# 1-Schematic_CarFan_controller_v2_3.net
KiCad netlist of a schematic drawn in EasyEDA
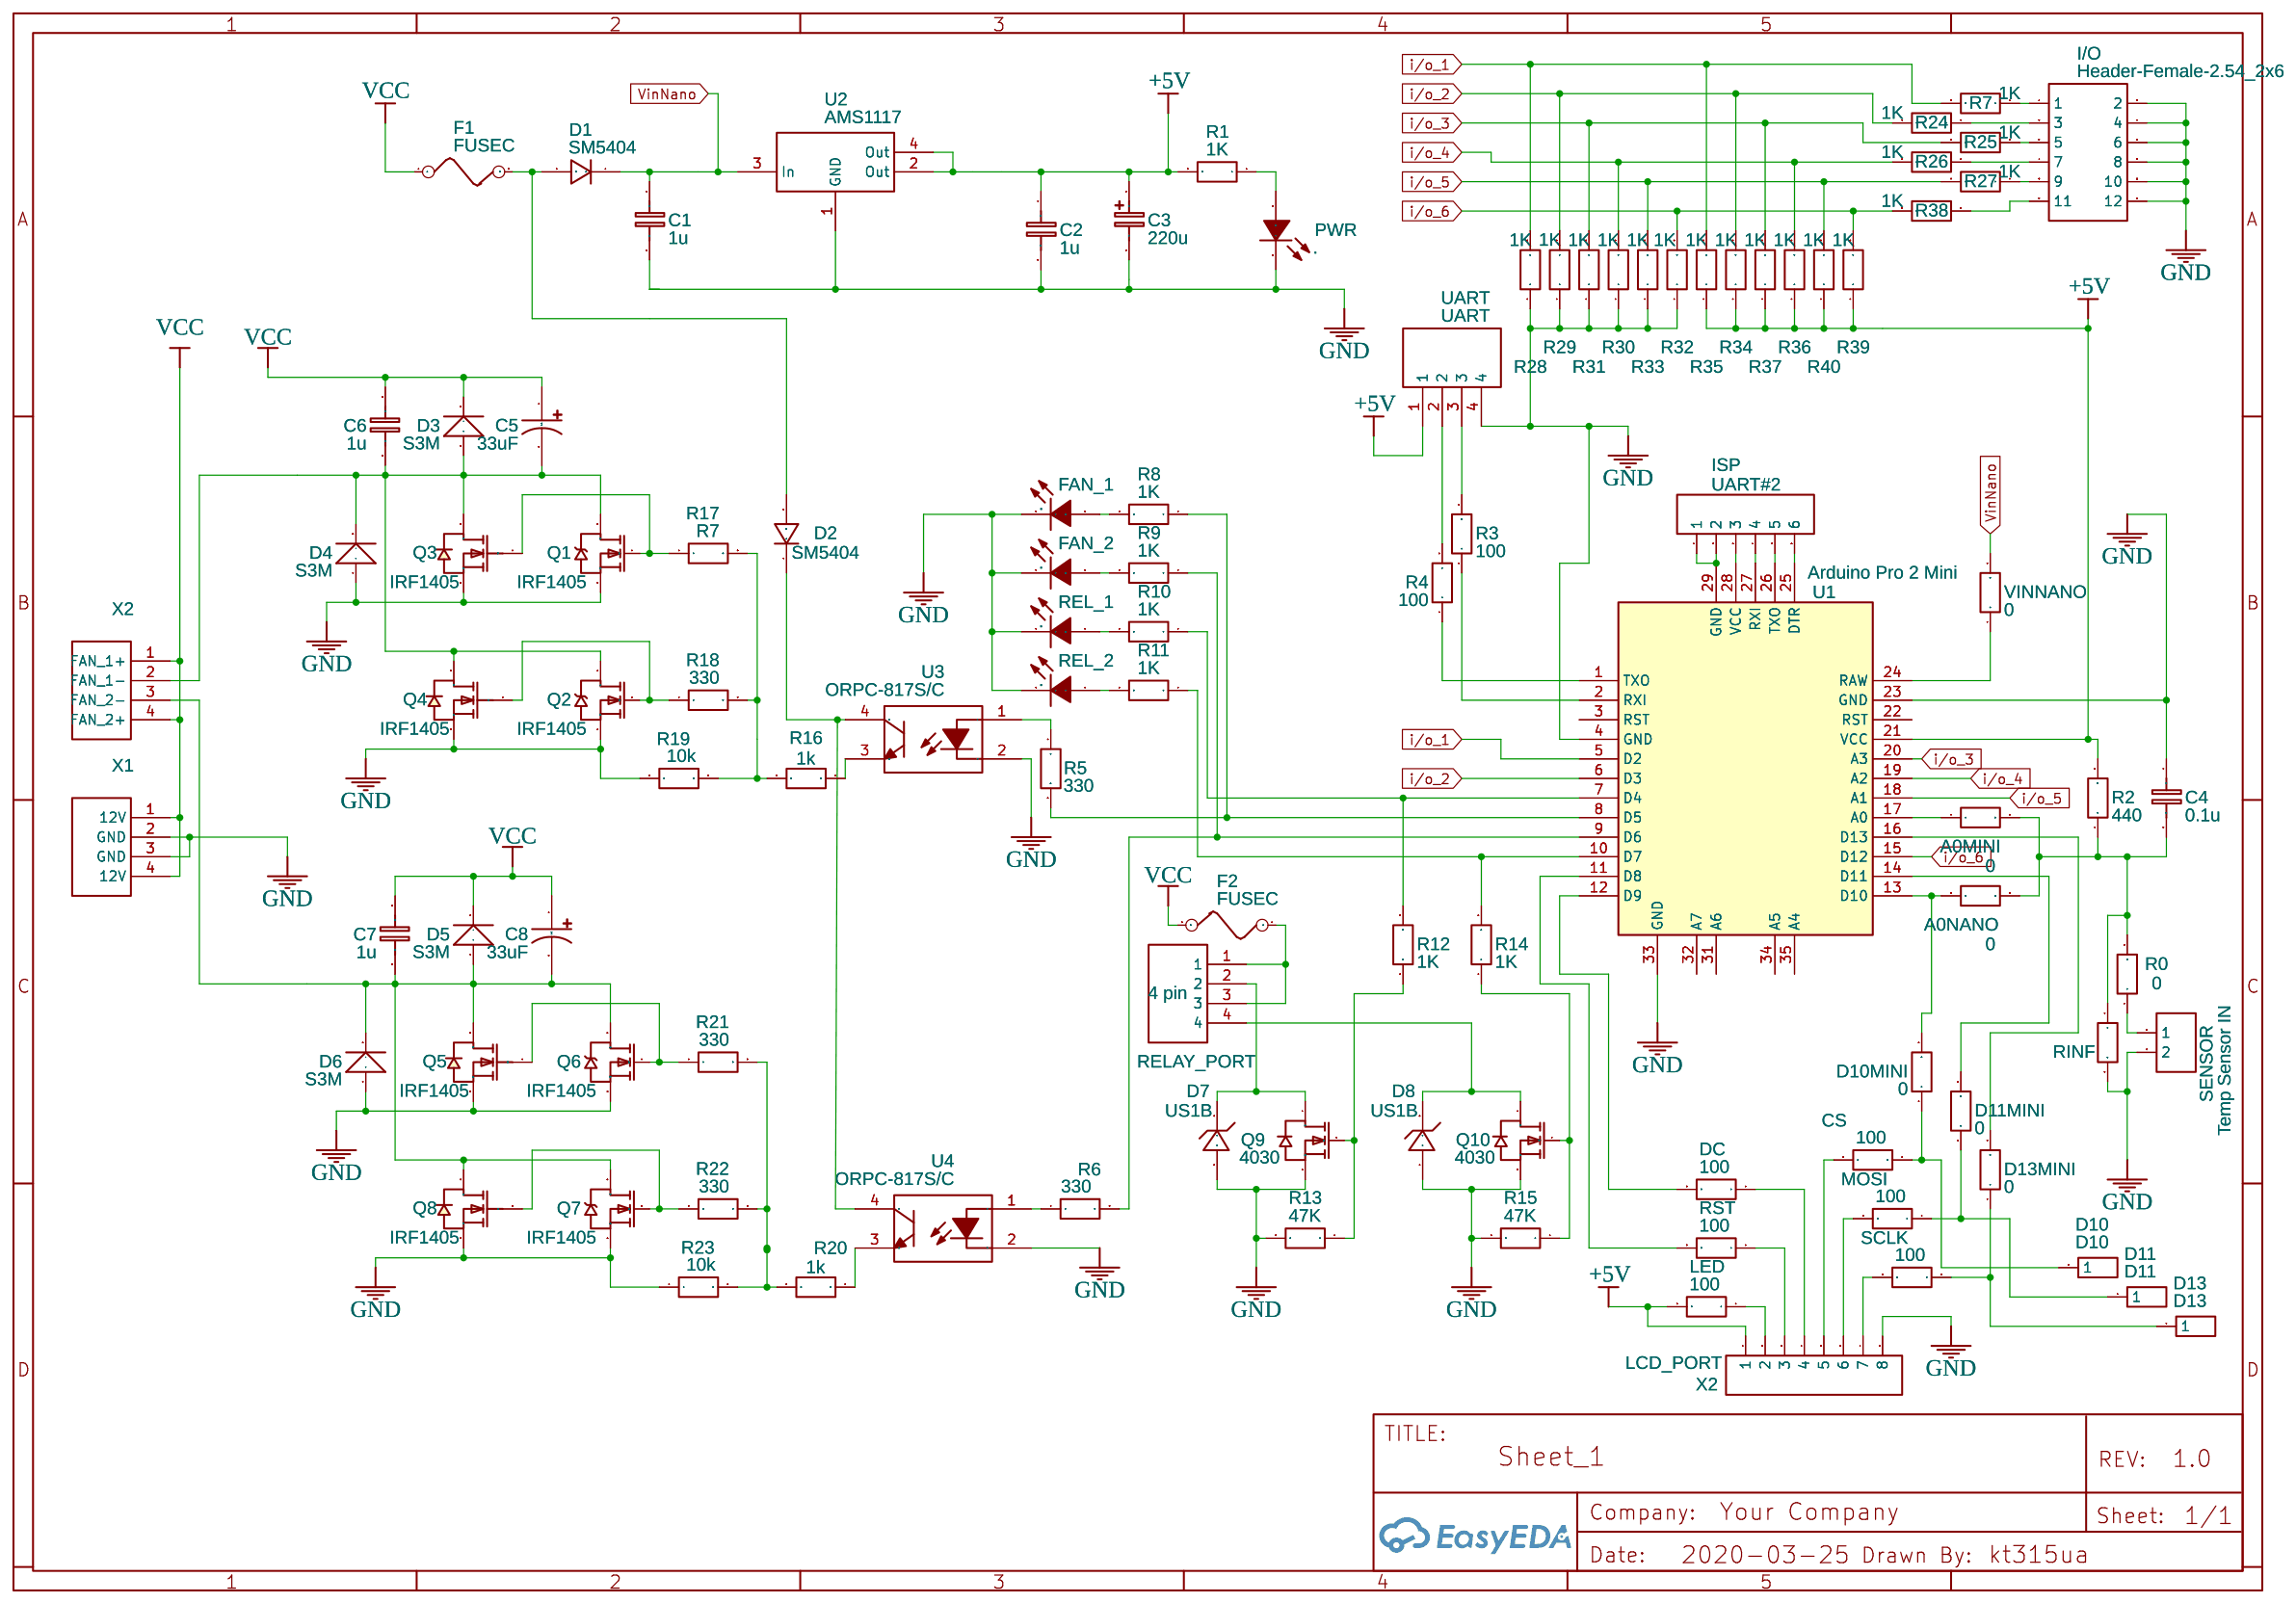
[diagram p0: schematic sheet]

(export (version "E")
  (design (tool "Eeschema 10.0.6"))
  (components
    (comp (ref "A0MINI") (value "0") (libsource (lib "") (part "Res_1206(1/4W)_EU_15")))
    (comp (ref "A0NANO") (value "0") (libsource (lib "") (part "Res_1206(1/4W)_EU_14")))
    (comp (ref "C1") (value "1u") (libsource (lib "") (part "Cap_1206_EU_3")))
    (comp (ref "C2") (value "1u") (libsource (lib "") (part "Cap_1206_EU_1")))
    (comp (ref "C3") (value "220u") (libsource (lib "") (part "Cap_Electrolytic(SMD)_D6.3XH5.5_EU")))
    (comp (ref "C4") (value "0.1u") (libsource (lib "") (part "Cap_1206_EU")))
    (comp (ref "C5")
      (value "33uF")
      (fields
        (field (name "BOM_Manufacturer Part") "EEEFK2A330P")
        (field (name "BOM_Supplier Part") "C178571")
      )
      (libsource (lib "") (part "EEEFK2A330P"))
    )
    (comp (ref "C6") (value "1u") (libsource (lib "") (part "Cap_1206_EU_2")))
    (comp (ref "C7") (value "1u") (libsource (lib "") (part "Cap_1206_EU_4")))
    (comp (ref "C8")
      (value "33uF")
      (fields
        (field (name "BOM_Manufacturer Part") "EEEFK2A330P")
        (field (name "BOM_Supplier Part") "C178571")
      )
      (libsource (lib "") (part "EEEFK2A330P"))
    )
    (comp (ref "CS") (value "100") (libsource (lib "") (part "Res_1206(1/4W)_EU_5")))
    (comp (ref "D1")
      (value "SM5404")
      (fields (field (name "BOM_Supplier Part") "C212808"))
      (libsource (lib "") (part "SM5404"))
    )
    (comp (ref "D2")
      (value "SM5404")
      (fields (field (name "BOM_Supplier Part") "C212808"))
      (libsource (lib "") (part "SM5404_1"))
    )
    (comp (ref "D3") (value "S3M") (libsource (lib "") (part "DDO-214AB")))
    (comp (ref "D4") (value "S3M") (libsource (lib "") (part "DDO-214AB")))
    (comp (ref "D5") (value "S3M") (libsource (lib "") (part "DDO-214AB")))
    (comp (ref "D6") (value "S3M") (libsource (lib "") (part "DDO-214AB")))
    (comp (ref "D7")
      (value "US1B")
      (fields
        (field (name "BOM_Manufacturer Part") "SMAZ12-13-F")
        (field (name "BOM_Supplier Part") "C110523")
      )
      (libsource (lib "") (part "SMAZ12-13-F(SMA(DO-214AC))"))
    )
    (comp (ref "D8")
      (value "US1B")
      (fields
        (field (name "BOM_Manufacturer Part") "SMAZ12-13-F")
        (field (name "BOM_Supplier Part") "C110523")
      )
      (libsource (lib "") (part "SMAZ12-13-F(SMA(DO-214AC))"))
    )
    (comp (ref "D10")
      (value "D10")
      (fields
        (field (name "BOM_Manufacturer Part") "Header-Male-2.54_1x1")
        (field (name "BOM_Supplier Part") "C81276")
      )
      (libsource (lib "") (part "Header-Male-2.54_1x1"))
    )
    (comp (ref "D10MINI") (value "0") (libsource (lib "") (part "Res_1206(1/4W)_EU_16")))
    (comp (ref "D11")
      (value "D11")
      (fields
        (field (name "BOM_Manufacturer Part") "Header-Male-2.54_1x1")
        (field (name "BOM_Supplier Part") "C81276")
      )
      (libsource (lib "") (part "Header-Male-2.54_1x1"))
    )
    (comp (ref "D11MINI") (value "0") (libsource (lib "") (part "Res_1206(1/4W)_EU_6")))
    (comp (ref "D13")
      (value "D13")
      (fields
        (field (name "BOM_Manufacturer Part") "Header-Male-2.54_1x1")
        (field (name "BOM_Supplier Part") "C81276")
      )
      (libsource (lib "") (part "Header-Male-2.54_1x1"))
    )
    (comp (ref "D13MINI") (value "0") (libsource (lib "") (part "Res_1206(1/4W)_EU_7")))
    (comp (ref "DC") (value "100") (libsource (lib "") (part "Res_1206(1/4W)_EU_12")))
    (comp (ref "F1") (value "FUSEC") (libsource (lib "") (part "FUSEC_1")))
    (comp (ref "F2") (value "FUSEC") (libsource (lib "") (part "FUSEC")))
    (comp (ref "FAN_1")
      (value ".")
      (fields
        (field (name "BOM_Manufacturer Part") "KT-1206Red LED")
        (field (name "BOM_Supplier Part") "C49018")
      )
      (libsource (lib "") (part "KT-1206Red LED_2"))
    )
    (comp (ref "FAN_2")
      (value ".")
      (fields
        (field (name "BOM_Manufacturer Part") "KT-1206Red LED")
        (field (name "BOM_Supplier Part") "C49018")
      )
      (libsource (lib "") (part "KT-1206Red LED_2"))
    )
    (comp (ref "I/O")
      (value "Header-Female-2.54_2x6")
      (fields (field (name "BOM_Supplier Part") "C36191"))
      (libsource (lib "") (part "Header-Female-2.54_2x6"))
    )
    (comp (ref "ISP")
      (value "UART#2")
      (fields
        (field (name "BOM_Manufacturer Part") "Female header 1*6p")
        (field (name "BOM_Supplier Part") "C40877")
      )
      (libsource (lib "") (part "Header-Female-2.54_1x6"))
    )
    (comp (ref "LCD_PORT")
      (value "X2")
      (fields
        (field (name "BOM_Manufacturer Part") "Female headerHDR1X8-2.54")
        (field (name "BOM_Supplier Part") "C27438")
      )
      (libsource (lib "") (part "Header-Female-2.54_1x8"))
    )
    (comp (ref "LED") (value "100") (libsource (lib "") (part "Res_1206(1/4W)_EU_9")))
    (comp (ref "MOSI") (value "100") (libsource (lib "") (part "Res_1206(1/4W)_EU_8")))
    (comp (ref "PWR")
      (value ".")
      (fields
        (field (name "BOM_Manufacturer Part") "KT-1206Red LED")
        (field (name "BOM_Supplier Part") "C49018")
      )
      (libsource (lib "") (part "KT-1206Red LED_1"))
    )
    (comp (ref "Q1")
      (value "IRF1405")
      (fields
        (field (name "BOM_Manufacturer Part") "IRF1405ZSTRLPBF")
        (field (name "BOM_Supplier Part") "C459941")
      )
      (libsource (lib "") (part "IRF1405ZSTRLPBF"))
    )
    (comp (ref "Q2")
      (value "IRF1405")
      (fields
        (field (name "BOM_Manufacturer Part") "IRF1405ZSTRLPBF")
        (field (name "BOM_Supplier Part") "C459941")
      )
      (libsource (lib "") (part "IRF1405ZSTRLPBF"))
    )
    (comp (ref "Q3")
      (value "IRF1405")
      (fields (field (name "BOM_Manufacturer Part") "IRF1405PBF") (field (name "BOM_Supplier Part") "C2559"))
      (libsource (lib "") (part "IRF1405PBF"))
    )
    (comp (ref "Q4")
      (value "IRF1405")
      (fields (field (name "BOM_Manufacturer Part") "IRF1405PBF") (field (name "BOM_Supplier Part") "C2559"))
      (libsource (lib "") (part "IRF1405PBF"))
    )
    (comp (ref "Q5")
      (value "IRF1405")
      (fields (field (name "BOM_Manufacturer Part") "IRF1405PBF") (field (name "BOM_Supplier Part") "C2559"))
      (libsource (lib "") (part "IRF1405PBF"))
    )
    (comp (ref "Q6")
      (value "IRF1405")
      (fields
        (field (name "BOM_Manufacturer Part") "IRF1405ZSTRLPBF")
        (field (name "BOM_Supplier Part") "C459941")
      )
      (libsource (lib "") (part "IRF1405ZSTRLPBF"))
    )
    (comp (ref "Q7")
      (value "IRF1405")
      (fields
        (field (name "BOM_Manufacturer Part") "IRF1405ZSTRLPBF")
        (field (name "BOM_Supplier Part") "C459941")
      )
      (libsource (lib "") (part "IRF1405ZSTRLPBF"))
    )
    (comp (ref "Q8")
      (value "IRF1405")
      (fields (field (name "BOM_Manufacturer Part") "IRF1405PBF") (field (name "BOM_Supplier Part") "C2559"))
      (libsource (lib "") (part "IRF1405PBF"))
    )
    (comp (ref "Q9")
      (value "4030")
      (fields
        (field (name "BOM_Manufacturer Part") "STD8N60DM2")
        (field (name "BOM_Supplier Part") "C457504")
      )
      (libsource (lib "") (part "STD8N60DM2"))
    )
    (comp (ref "Q10")
      (value "4030")
      (fields
        (field (name "BOM_Manufacturer Part") "STD8N60DM2")
        (field (name "BOM_Supplier Part") "C457504")
      )
      (libsource (lib "") (part "STD8N60DM2"))
    )
    (comp (ref "R0") (value "0") (libsource (lib "") (part "Res_1206(1/4W)_EU_2")))
    (comp (ref "R1") (value "1K") (libsource (lib "") (part "Res_1206(1/4W)_EU")))
    (comp (ref "R2") (value "440") (libsource (lib "") (part "Res_1206(1/4W)_EU_2")))
    (comp (ref "R3") (value "100") (libsource (lib "") (part "Res_1206(1/4W)_EU_2")))
    (comp (ref "R4") (value "100") (libsource (lib "") (part "Res_1206(1/4W)_EU_2")))
    (comp (ref "R5") (value "330") (libsource (lib "") (part "Res_1206(1/4W)_EU_10")))
    (comp (ref "R6") (value "330") (libsource (lib "") (part "Res_1206(1/4W)_EU_3")))
    (comp (ref "R7") (value "1K") (libsource (lib "") (part "Res_1206(1/4W)_EU")))
    (comp (ref "R8") (value "1K") (libsource (lib "") (part "Res_1206(1/4W)_EU")))
    (comp (ref "R9") (value "1K") (libsource (lib "") (part "Res_1206(1/4W)_EU")))
    (comp (ref "R10") (value "1K") (libsource (lib "") (part "Res_1206(1/4W)_EU")))
    (comp (ref "R11") (value "1K") (libsource (lib "") (part "Res_1206(1/4W)_EU")))
    (comp (ref "R12") (value "1K") (libsource (lib "") (part "Res_1206(1/4W)_EU_2")))
    (comp (ref "R13") (value "47K") (libsource (lib "") (part "Res_1206(1/4W)_EU")))
    (comp (ref "R14") (value "1K") (libsource (lib "") (part "Res_1206(1/4W)_EU_2")))
    (comp (ref "R15") (value "47K") (libsource (lib "") (part "Res_1206(1/4W)_EU")))
    (comp (ref "R16") (value "1k") (libsource (lib "") (part "Res_1206(1/4W)_EU")))
    (comp (ref "R17") (value "R7") (libsource (lib "") (part "Res_1206(1/4W)_EU_3")))
    (comp (ref "R18") (value "330") (libsource (lib "") (part "Res_1206(1/4W)_EU_3")))
    (comp (ref "R19") (value "10k") (libsource (lib "") (part "Res_1206(1/4W)_EU_3")))
    (comp (ref "R20") (value "1k") (libsource (lib "") (part "Res_1206(1/4W)_EU")))
    (comp (ref "R21") (value "330") (libsource (lib "") (part "Res_1206(1/4W)_EU_3")))
    (comp (ref "R22") (value "330") (libsource (lib "") (part "Res_1206(1/4W)_EU_3")))
    (comp (ref "R23") (value "10k") (libsource (lib "") (part "Res_1206(1/4W)_EU_3")))
    (comp (ref "R24") (value "1K") (libsource (lib "") (part "Res_1206(1/4W)_EU")))
    (comp (ref "R25") (value "1K") (libsource (lib "") (part "Res_1206(1/4W)_EU")))
    (comp (ref "R26") (value "1K") (libsource (lib "") (part "Res_1206(1/4W)_EU")))
    (comp (ref "R27") (value "1K") (libsource (lib "") (part "Res_1206(1/4W)_EU")))
    (comp (ref "R28") (value "1K") (libsource (lib "") (part "Res_1206(1/4W)_EU_2")))
    (comp (ref "R29") (value "1K") (libsource (lib "") (part "Res_1206(1/4W)_EU_2")))
    (comp (ref "R30") (value "1K") (libsource (lib "") (part "Res_1206(1/4W)_EU_2")))
    (comp (ref "R31") (value "1K") (libsource (lib "") (part "Res_1206(1/4W)_EU_2")))
    (comp (ref "R32") (value "1K") (libsource (lib "") (part "Res_1206(1/4W)_EU_2")))
    (comp (ref "R33") (value "1K") (libsource (lib "") (part "Res_1206(1/4W)_EU_2")))
    (comp (ref "R34") (value "1K") (libsource (lib "") (part "Res_1206(1/4W)_EU_2")))
    (comp (ref "R35") (value "1K") (libsource (lib "") (part "Res_1206(1/4W)_EU_2")))
    (comp (ref "R36") (value "1K") (libsource (lib "") (part "Res_1206(1/4W)_EU_2")))
    (comp (ref "R37") (value "1K") (libsource (lib "") (part "Res_1206(1/4W)_EU_2")))
    (comp (ref "R38") (value "1K") (libsource (lib "") (part "Res_1206(1/4W)_EU")))
    (comp (ref "R39") (value "1K") (libsource (lib "") (part "Res_1206(1/4W)_EU_2")))
    (comp (ref "R40") (value "1K") (libsource (lib "") (part "Res_1206(1/4W)_EU_2")))
    (comp (ref "RELAY_PORT")
      (value "4 pin")
      (fields
        (field (name "BOM_Manufacturer Part") "220S-1*4P H=8.5MM Ytype Gold-plated")
        (field (name "BOM_Supplier Part") "C124413")
      )
      (libsource (lib "") (part "220S-1*4P H=8.5MM Ytype Gold-plated"))
    )
    (comp (ref "REL_1")
      (value ".")
      (fields
        (field (name "BOM_Manufacturer Part") "KT-1206Red LED")
        (field (name "BOM_Supplier Part") "C49018")
      )
      (libsource (lib "") (part "KT-1206Red LED"))
    )
    (comp (ref "REL_2")
      (value ".")
      (fields
        (field (name "BOM_Manufacturer Part") "KT-1206Red LED")
        (field (name "BOM_Supplier Part") "C49018")
      )
      (libsource (lib "") (part "KT-1206Red LED"))
    )
    (comp (ref "RINF") (value "0") (libsource (lib "") (part "Res_1206(1/4W)_EU_11")))
    (comp (ref "RST") (value "100") (libsource (lib "") (part "Res_1206(1/4W)_EU_1")))
    (comp (ref "SCLK") (value "100") (libsource (lib "") (part "Res_1206(1/4W)_EU_13")))
    (comp (ref "SENSOR")
      (value "Temp Sensor IN")
      (fields
        (field (name "BOM_Manufacturer Part") "2.54-1*2PFemale")
        (field (name "BOM_Supplier Part") "C49661")
      )
      (libsource (lib "") (part "Header-Female-2.54_1x2"))
    )
    (comp (ref "U1") (value "Arduino Pro 2 Mini") (libsource (lib "") (part "Arduino Pro 2 Mini_328_-_3.3V")))
    (comp (ref "U2")
      (value "AMS1117")
      (fields (field (name "BOM_Supplier Part") "C6186"))
      (libsource (lib "") (part "AMS1117"))
    )
    (comp (ref "U3")
      (value "ORPC-817S/C")
      (fields (field (name "BOM_Supplier Part") "C231230"))
      (libsource (lib "") (part "ORPC-817S/C"))
    )
    (comp (ref "U4")
      (value "ORPC-817S/C")
      (fields (field (name "BOM_Supplier Part") "C231230"))
      (libsource (lib "") (part "ORPC-817S/C"))
    )
    (comp (ref "UART")
      (value "UART")
      (fields
        (field (name "BOM_Manufacturer Part") "220S-1*4P H=8.5MM Ytype Gold-plated")
        (field (name "BOM_Supplier Part") "C124413")
      )
      (libsource (lib "") (part "220S-1*4P H=8.5MM Ytype Gold-plated_1"))
    )
    (comp (ref "VINNANO") (value "0") (libsource (lib "") (part "Res_1206(1/4W)_EU_4")))
    (comp (ref "X1")
      (value "AMP_MATE_N_LOK")
      (fields (field (name "BOM_Manufacturer Part") "350424-1") (field (name "BOM_Supplier Part") "718-9605"))
      (libsource (lib "") (part "AMP_MATE_N_LOK"))
    )
    (comp (ref "X2")
      (value "AMP_MATE_N_LOK")
      (fields (field (name "BOM_Manufacturer Part") "350424-1") (field (name "BOM_Supplier Part") "718-9605"))
      (libsource (lib "") (part "AMP_MATE_N_LOK_1"))
    )
  )
  (nets
    (net (code "1") (name "+5V") (class "Default")
      (node (ref "C2") (pin "1") (pinfunction "1_1") (pintype "unspecified"))
      (node (ref "C3") (pin "1") (pinfunction "1_1") (pintype "unspecified"))
      (node (ref "LCD_PORT") (pin "1") (pinfunction "1_1") (pintype "input"))
      (node (ref "LED") (pin "2") (pinfunction "2_2") (pintype "unspecified"))
      (node (ref "R1") (pin "2") (pinfunction "2_2") (pintype "unspecified"))
      (node (ref "R2") (pin "2") (pinfunction "2_2") (pintype "unspecified"))
      (node (ref "R34") (pin "1") (pinfunction "1_1") (pintype "unspecified"))
      (node (ref "R35") (pin "1") (pinfunction "1_1") (pintype "unspecified"))
      (node (ref "R36") (pin "1") (pinfunction "1_1") (pintype "unspecified"))
      (node (ref "R37") (pin "1") (pinfunction "1_1") (pintype "unspecified"))
      (node (ref "R39") (pin "1") (pinfunction "1_1") (pintype "unspecified"))
      (node (ref "R40") (pin "1") (pinfunction "1_1") (pintype "unspecified"))
      (node (ref "U1") (pin "21") (pinfunction "VCC_21") (pintype "unspecified"))
      (node (ref "U2") (pin "2") (pinfunction "Out_2") (pintype "unspecified"))
      (node (ref "U2") (pin "4") (pinfunction "Out_4") (pintype "unspecified"))
      (node (ref "UART") (pin "1") (pinfunction "1_1") (pintype "unspecified"))
    )
    (net (code "2") (name "GND") (class "Default")
      (node (ref "C1") (pin "2") (pinfunction "2_2") (pintype "unspecified"))
      (node (ref "C2") (pin "2") (pinfunction "2_2") (pintype "unspecified"))
      (node (ref "C3") (pin "2") (pinfunction "2_2") (pintype "unspecified"))
      (node (ref "C4") (pin "1") (pinfunction "1_1") (pintype "unspecified"))
      (node (ref "D4") (pin "1") (pinfunction "+_1") (pintype "unspecified"))
      (node (ref "D6") (pin "1") (pinfunction "+_1") (pintype "unspecified"))
      (node (ref "D7") (pin "1") (pinfunction "A_1") (pintype "unspecified"))
      (node (ref "D8") (pin "1") (pinfunction "A_1") (pintype "unspecified"))
      (node (ref "FAN_1") (pin "2") (pinfunction "K_2") (pintype "unspecified"))
      (node (ref "FAN_2") (pin "2") (pinfunction "K_2") (pintype "unspecified"))
      (node (ref "I/O") (pin "10") (pinfunction "10_10") (pintype "input"))
      (node (ref "I/O") (pin "12") (pinfunction "12_12") (pintype "input"))
      (node (ref "I/O") (pin "2") (pinfunction "2_2") (pintype "input"))
      (node (ref "I/O") (pin "4") (pinfunction "4_4") (pintype "input"))
      (node (ref "I/O") (pin "6") (pinfunction "6_6") (pintype "input"))
      (node (ref "I/O") (pin "8") (pinfunction "8_8") (pintype "input"))
      (node (ref "LCD_PORT") (pin "8") (pinfunction "8_8") (pintype "input"))
      (node (ref "PWR") (pin "2") (pinfunction "K_2") (pintype "unspecified"))
      (node (ref "Q1") (pin "3") (pinfunction "S_3") (pintype "unspecified"))
      (node (ref "Q10") (pin "3") (pinfunction "S_3") (pintype "unspecified"))
      (node (ref "Q2") (pin "3") (pinfunction "S_3") (pintype "unspecified"))
      (node (ref "Q3") (pin "3") (pinfunction "S_3") (pintype "unspecified"))
      (node (ref "Q4") (pin "3") (pinfunction "S_3") (pintype "unspecified"))
      (node (ref "Q5") (pin "3") (pinfunction "S_3") (pintype "unspecified"))
      (node (ref "Q6") (pin "3") (pinfunction "S_3") (pintype "unspecified"))
      (node (ref "Q7") (pin "3") (pinfunction "S_3") (pintype "unspecified"))
      (node (ref "Q8") (pin "3") (pinfunction "S_3") (pintype "unspecified"))
      (node (ref "Q9") (pin "3") (pinfunction "S_3") (pintype "unspecified"))
      (node (ref "R13") (pin "2") (pinfunction "2_2") (pintype "unspecified"))
      (node (ref "R15") (pin "2") (pinfunction "2_2") (pintype "unspecified"))
      (node (ref "R19") (pin "1") (pinfunction "1_1") (pintype "unspecified"))
      (node (ref "R23") (pin "1") (pinfunction "1_1") (pintype "unspecified"))
      (node (ref "R28") (pin "1") (pinfunction "1_1") (pintype "unspecified"))
      (node (ref "R29") (pin "1") (pinfunction "1_1") (pintype "unspecified"))
      (node (ref "R30") (pin "1") (pinfunction "1_1") (pintype "unspecified"))
      (node (ref "R31") (pin "1") (pinfunction "1_1") (pintype "unspecified"))
      (node (ref "R32") (pin "1") (pinfunction "1_1") (pintype "unspecified"))
      (node (ref "R33") (pin "1") (pinfunction "1_1") (pintype "unspecified"))
      (node (ref "REL_1") (pin "2") (pinfunction "K_2") (pintype "unspecified"))
      (node (ref "REL_2") (pin "2") (pinfunction "K_2") (pintype "unspecified"))
      (node (ref "RINF") (pin "2") (pinfunction "2_2") (pintype "unspecified"))
      (node (ref "SENSOR") (pin "2") (pinfunction "2_2") (pintype "input"))
      (node (ref "U1") (pin "23") (pinfunction "GND_23") (pintype "unspecified"))
      (node (ref "U1") (pin "33") (pinfunction "GND_33") (pintype "unspecified"))
      (node (ref "U1") (pin "4") (pinfunction "GND_4") (pintype "unspecified"))
      (node (ref "U2") (pin "1") (pinfunction "GND_1") (pintype "unspecified"))
      (node (ref "U3") (pin "2") (pinfunction "2_2") (pintype "unspecified"))
      (node (ref "U4") (pin "2") (pinfunction "2_2") (pintype "unspecified"))
      (node (ref "UART") (pin "4") (pinfunction "4_4") (pintype "unspecified"))
      (node (ref "X1") (pin "2") (pinfunction "GND_2") (pintype "unspecified"))
      (node (ref "X1") (pin "3") (pinfunction "GND_3") (pintype "unspecified"))
    )
    (net (code "3") (name "Net-(A0MINI-Pad2)") (class "Default")
      (node (ref "A0MINI") (pin "2") (pinfunction "2_2") (pintype "unspecified"))
      (node (ref "A0NANO") (pin "2") (pinfunction "2_2") (pintype "unspecified"))
      (node (ref "C4") (pin "2") (pinfunction "2_2") (pintype "unspecified"))
      (node (ref "R0") (pin "2") (pinfunction "2_2") (pintype "unspecified"))
      (node (ref "R2") (pin "1") (pinfunction "1_1") (pintype "unspecified"))
      (node (ref "RINF") (pin "1") (pinfunction "1_1") (pintype "unspecified"))
    )
    (net (code "4") (name "Net-(CS-Pad1)") (class "Default")
      (node (ref "CS") (pin "1") (pinfunction "1_1") (pintype "unspecified"))
      (node (ref "D10") (pin "1") (pinfunction "1_1") (pintype "input"))
      (node (ref "D10MINI") (pin "1") (pinfunction "1_1") (pintype "unspecified"))
    )
    (net (code "5") (name "Net-(CS-Pad2)") (class "Default")
      (node (ref "CS") (pin "2") (pinfunction "2_2") (pintype "unspecified"))
      (node (ref "LCD_PORT") (pin "5") (pinfunction "5_5") (pintype "input"))
    )
    (net (code "6") (name "Net-(D1-Pad2)") (class "Default")
      (node (ref "D1") (pin "2") (pinfunction "2_2") (pintype "unspecified"))
      (node (ref "D2") (pin "2") (pinfunction "2_2") (pintype "unspecified"))
      (node (ref "F1") (pin "2") (pinfunction "2_2") (pintype "unspecified"))
    )
    (net (code "7") (name "Net-(D2-Pad1)") (class "Default")
      (node (ref "D2") (pin "1") (pinfunction "1_1") (pintype "unspecified"))
      (node (ref "U3") (pin "4") (pinfunction "4_4") (pintype "unspecified"))
      (node (ref "U4") (pin "4") (pinfunction "4_4") (pintype "unspecified"))
    )
    (net (code "8") (name "Net-(D3-+)") (class "Default")
      (node (ref "C5") (pin "2") (pinfunction "2_2") (pintype "unspecified"))
      (node (ref "C6") (pin "2") (pinfunction "2_2") (pintype "unspecified"))
      (node (ref "D3") (pin "1") (pinfunction "+_1") (pintype "unspecified"))
      (node (ref "D4") (pin "2") (pinfunction "-_2") (pintype "unspecified"))
      (node (ref "Q1") (pin "2") (pinfunction "D_2") (pintype "unspecified"))
      (node (ref "Q2") (pin "2") (pinfunction "D_2") (pintype "unspecified"))
      (node (ref "Q3") (pin "2") (pinfunction "D_2") (pintype "unspecified"))
      (node (ref "Q4") (pin "2") (pinfunction "D_2") (pintype "unspecified"))
      (node (ref "X2") (pin "2") (pinfunction "FAN_1-_2") (pintype "unspecified"))
    )
    (net (code "9") (name "Net-(D5-+)") (class "Default")
      (node (ref "C7") (pin "2") (pinfunction "2_2") (pintype "unspecified"))
      (node (ref "C8") (pin "2") (pinfunction "2_2") (pintype "unspecified"))
      (node (ref "D5") (pin "1") (pinfunction "+_1") (pintype "unspecified"))
      (node (ref "D6") (pin "2") (pinfunction "-_2") (pintype "unspecified"))
      (node (ref "Q5") (pin "2") (pinfunction "D_2") (pintype "unspecified"))
      (node (ref "Q6") (pin "2") (pinfunction "D_2") (pintype "unspecified"))
      (node (ref "Q7") (pin "2") (pinfunction "D_2") (pintype "unspecified"))
      (node (ref "Q8") (pin "2") (pinfunction "D_2") (pintype "unspecified"))
      (node (ref "X2") (pin "3") (pinfunction "FAN_2-_3") (pintype "unspecified"))
    )
    (net (code "10") (name "Net-(D7-K)") (class "Default")
      (node (ref "D7") (pin "2") (pinfunction "K_2") (pintype "unspecified"))
      (node (ref "Q9") (pin "4") (pinfunction "D_4") (pintype "unspecified"))
      (node (ref "RELAY_PORT") (pin "2") (pinfunction "2_2") (pintype "unspecified"))
    )
    (net (code "11") (name "Net-(D8-K)") (class "Default")
      (node (ref "D8") (pin "2") (pinfunction "K_2") (pintype "unspecified"))
      (node (ref "Q10") (pin "4") (pinfunction "D_4") (pintype "unspecified"))
      (node (ref "RELAY_PORT") (pin "4") (pinfunction "4_4") (pintype "unspecified"))
    )
    (net (code "12") (name "Net-(D11-Pad1)") (class "Default")
      (node (ref "D11") (pin "1") (pinfunction "1_1") (pintype "input"))
      (node (ref "D11MINI") (pin "1") (pinfunction "1_1") (pintype "unspecified"))
      (node (ref "MOSI") (pin "1") (pinfunction "1_1") (pintype "unspecified"))
    )
    (net (code "13") (name "Net-(D13-Pad1)") (class "Default")
      (node (ref "D13") (pin "1") (pinfunction "1_1") (pintype "input"))
      (node (ref "D13MINI") (pin "1") (pinfunction "1_1") (pintype "unspecified"))
      (node (ref "SCLK") (pin "1") (pinfunction "1_1") (pintype "unspecified"))
    )
    (net (code "14") (name "Net-(DC-Pad1)") (class "Default")
      (node (ref "DC") (pin "1") (pinfunction "1_1") (pintype "unspecified"))
      (node (ref "LCD_PORT") (pin "4") (pinfunction "4_4") (pintype "input"))
    )
    (net (code "15") (name "Net-(F2-Pad1)") (class "Default")
      (node (ref "F2") (pin "1") (pinfunction "1_1") (pintype "unspecified"))
      (node (ref "RELAY_PORT") (pin "1") (pinfunction "1_1") (pintype "unspecified"))
      (node (ref "RELAY_PORT") (pin "3") (pinfunction "3_3") (pintype "unspecified"))
    )
    (net (code "16") (name "Net-(FAN_1-A)") (class "Default")
      (node (ref "FAN_1") (pin "1") (pinfunction "A_1") (pintype "unspecified"))
      (node (ref "R8") (pin "2") (pinfunction "2_2") (pintype "unspecified"))
    )
    (net (code "17") (name "Net-(FAN_2-A)") (class "Default")
      (node (ref "FAN_2") (pin "1") (pinfunction "A_1") (pintype "unspecified"))
      (node (ref "R9") (pin "2") (pinfunction "2_2") (pintype "unspecified"))
    )
    (net (code "18") (name "Net-(I/O-Pad1)") (class "Default")
      (node (ref "I/O") (pin "1") (pinfunction "1_1") (pintype "input"))
      (node (ref "R7") (pin "1") (pinfunction "1_1") (pintype "unspecified"))
    )
    (net (code "19") (name "Net-(I/O-Pad3)") (class "Default")
      (node (ref "I/O") (pin "3") (pinfunction "3_3") (pintype "input"))
      (node (ref "R24") (pin "1") (pinfunction "1_1") (pintype "unspecified"))
    )
    (net (code "20") (name "Net-(I/O-Pad5)") (class "Default")
      (node (ref "I/O") (pin "5") (pinfunction "5_5") (pintype "input"))
      (node (ref "R25") (pin "1") (pinfunction "1_1") (pintype "unspecified"))
    )
    (net (code "21") (name "Net-(I/O-Pad7)") (class "Default")
      (node (ref "I/O") (pin "7") (pinfunction "7_7") (pintype "input"))
      (node (ref "R26") (pin "1") (pinfunction "1_1") (pintype "unspecified"))
    )
    (net (code "22") (name "Net-(I/O-Pad9)") (class "Default")
      (node (ref "I/O") (pin "9") (pinfunction "9_9") (pintype "input"))
      (node (ref "R27") (pin "1") (pinfunction "1_1") (pintype "unspecified"))
    )
    (net (code "23") (name "Net-(I/O-Pad11)") (class "Default")
      (node (ref "I/O") (pin "11") (pinfunction "11_11") (pintype "input"))
      (node (ref "R38") (pin "1") (pinfunction "1_1") (pintype "unspecified"))
    )
    (net (code "24") (name "Net-(ISP-Pad1)") (class "Default")
      (node (ref "ISP") (pin "1") (pinfunction "1_1") (pintype "input"))
      (node (ref "ISP") (pin "2") (pinfunction "2_2") (pintype "input"))
      (node (ref "U1") (pin "29") (pinfunction "GND_29") (pintype "unspecified"))
    )
    (net (code "25") (name "Net-(ISP-Pad3)") (class "Default")
      (node (ref "ISP") (pin "3") (pinfunction "3_3") (pintype "input"))
      (node (ref "U1") (pin "28") (pinfunction "VCC_28") (pintype "unspecified"))
    )
    (net (code "26") (name "Net-(ISP-Pad4)") (class "Default")
      (node (ref "ISP") (pin "4") (pinfunction "4_4") (pintype "input"))
      (node (ref "U1") (pin "27") (pinfunction "RXI_27") (pintype "unspecified"))
    )
    (net (code "27") (name "Net-(ISP-Pad5)") (class "Default")
      (node (ref "ISP") (pin "5") (pinfunction "5_5") (pintype "input"))
      (node (ref "U1") (pin "26") (pinfunction "TXO_26") (pintype "unspecified"))
    )
    (net (code "28") (name "Net-(LCD_PORT-Pad2)") (class "Default")
      (node (ref "LCD_PORT") (pin "2") (pinfunction "2_2") (pintype "input"))
      (node (ref "LED") (pin "1") (pinfunction "1_1") (pintype "unspecified"))
    )
    (net (code "29") (name "Net-(LCD_PORT-Pad3)") (class "Default")
      (node (ref "LCD_PORT") (pin "3") (pinfunction "3_3") (pintype "input"))
      (node (ref "RST") (pin "1") (pinfunction "1_1") (pintype "unspecified"))
    )
    (net (code "30") (name "Net-(LCD_PORT-Pad6)") (class "Default")
      (node (ref "LCD_PORT") (pin "6") (pinfunction "6_6") (pintype "input"))
      (node (ref "MOSI") (pin "2") (pinfunction "2_2") (pintype "unspecified"))
    )
    (net (code "31") (name "Net-(LCD_PORT-Pad7)") (class "Default")
      (node (ref "LCD_PORT") (pin "7") (pinfunction "7_7") (pintype "input"))
      (node (ref "SCLK") (pin "2") (pinfunction "2_2") (pintype "unspecified"))
    )
    (net (code "32") (name "Net-(PWR-A)") (class "Default")
      (node (ref "PWR") (pin "1") (pinfunction "A_1") (pintype "unspecified"))
      (node (ref "R1") (pin "1") (pinfunction "1_1") (pintype "unspecified"))
    )
    (net (code "33") (name "Net-(Q1-G)") (class "Default")
      (node (ref "Q1") (pin "1") (pinfunction "G_1") (pintype "unspecified"))
      (node (ref "Q3") (pin "1") (pinfunction "G_1") (pintype "unspecified"))
      (node (ref "R17") (pin "1") (pinfunction "1_1") (pintype "unspecified"))
    )
    (net (code "34") (name "Net-(Q2-G)") (class "Default")
      (node (ref "Q2") (pin "1") (pinfunction "G_1") (pintype "unspecified"))
      (node (ref "Q4") (pin "1") (pinfunction "G_1") (pintype "unspecified"))
      (node (ref "R18") (pin "1") (pinfunction "1_1") (pintype "unspecified"))
    )
    (net (code "35") (name "Net-(Q5-G)") (class "Default")
      (node (ref "Q5") (pin "1") (pinfunction "G_1") (pintype "unspecified"))
      (node (ref "Q6") (pin "1") (pinfunction "G_1") (pintype "unspecified"))
      (node (ref "R21") (pin "1") (pinfunction "1_1") (pintype "unspecified"))
    )
    (net (code "36") (name "Net-(Q7-G)") (class "Default")
      (node (ref "Q7") (pin "1") (pinfunction "G_1") (pintype "unspecified"))
      (node (ref "Q8") (pin "1") (pinfunction "G_1") (pintype "unspecified"))
      (node (ref "R22") (pin "1") (pinfunction "1_1") (pintype "unspecified"))
    )
    (net (code "37") (name "Net-(Q9-G)") (class "Default")
      (node (ref "Q9") (pin "1") (pinfunction "G_1") (pintype "unspecified"))
      (node (ref "R12") (pin "1") (pinfunction "1_1") (pintype "unspecified"))
      (node (ref "R13") (pin "1") (pinfunction "1_1") (pintype "unspecified"))
    )
    (net (code "38") (name "Net-(Q10-G)") (class "Default")
      (node (ref "Q10") (pin "1") (pinfunction "G_1") (pintype "unspecified"))
      (node (ref "R14") (pin "1") (pinfunction "1_1") (pintype "unspecified"))
      (node (ref "R15") (pin "1") (pinfunction "1_1") (pintype "unspecified"))
    )
    (net (code "39") (name "Net-(R0-Pad1)") (class "Default")
      (node (ref "R0") (pin "1") (pinfunction "1_1") (pintype "unspecified"))
      (node (ref "SENSOR") (pin "1") (pinfunction "1_1") (pintype "input"))
    )
    (net (code "40") (name "Net-(R3-Pad1)") (class "Default")
      (node (ref "R3") (pin "1") (pinfunction "1_1") (pintype "unspecified"))
      (node (ref "U1") (pin "2") (pinfunction "RXI_2") (pintype "unspecified"))
    )
    (net (code "41") (name "Net-(R3-Pad2)") (class "Default")
      (node (ref "R3") (pin "2") (pinfunction "2_2") (pintype "unspecified"))
      (node (ref "UART") (pin "3") (pinfunction "3_3") (pintype "unspecified"))
    )
    (net (code "42") (name "Net-(R4-Pad1)") (class "Default")
      (node (ref "R4") (pin "1") (pinfunction "1_1") (pintype "unspecified"))
      (node (ref "U1") (pin "1") (pinfunction "TXO_1") (pintype "unspecified"))
    )
    (net (code "43") (name "Net-(R4-Pad2)") (class "Default")
      (node (ref "R4") (pin "2") (pinfunction "2_2") (pintype "unspecified"))
      (node (ref "UART") (pin "2") (pinfunction "2_2") (pintype "unspecified"))
    )
    (net (code "44") (name "Net-(R5-Pad1)") (class "Default")
      (node (ref "R5") (pin "1") (pinfunction "1_1") (pintype "unspecified"))
      (node (ref "U3") (pin "1") (pinfunction "1_1") (pintype "unspecified"))
    )
    (net (code "45") (name "Net-(R6-Pad1)") (class "Default")
      (node (ref "R6") (pin "1") (pinfunction "1_1") (pintype "unspecified"))
      (node (ref "U4") (pin "1") (pinfunction "1_1") (pintype "unspecified"))
    )
    (net (code "46") (name "Net-(R16-Pad1)") (class "Default")
      (node (ref "R16") (pin "1") (pinfunction "1_1") (pintype "unspecified"))
      (node (ref "U3") (pin "3") (pinfunction "3_3") (pintype "unspecified"))
    )
    (net (code "47") (name "Net-(R16-Pad2)") (class "Default")
      (node (ref "R16") (pin "2") (pinfunction "2_2") (pintype "unspecified"))
      (node (ref "R17") (pin "2") (pinfunction "2_2") (pintype "unspecified"))
      (node (ref "R18") (pin "2") (pinfunction "2_2") (pintype "unspecified"))
      (node (ref "R19") (pin "2") (pinfunction "2_2") (pintype "unspecified"))
    )
    (net (code "48") (name "Net-(R20-Pad1)") (class "Default")
      (node (ref "R20") (pin "1") (pinfunction "1_1") (pintype "unspecified"))
      (node (ref "U4") (pin "3") (pinfunction "3_3") (pintype "unspecified"))
    )
    (net (code "49") (name "Net-(R20-Pad2)") (class "Default")
      (node (ref "R20") (pin "2") (pinfunction "2_2") (pintype "unspecified"))
      (node (ref "R21") (pin "2") (pinfunction "2_2") (pintype "unspecified"))
      (node (ref "R22") (pin "2") (pinfunction "2_2") (pintype "unspecified"))
      (node (ref "R23") (pin "2") (pinfunction "2_2") (pintype "unspecified"))
    )
    (net (code "50") (name "Net-(REL_1-A)") (class "Default")
      (node (ref "R10") (pin "2") (pinfunction "2_2") (pintype "unspecified"))
      (node (ref "REL_1") (pin "1") (pinfunction "A_1") (pintype "unspecified"))
    )
    (net (code "51") (name "Net-(REL_2-A)") (class "Default")
      (node (ref "R11") (pin "2") (pinfunction "2_2") (pintype "unspecified"))
      (node (ref "REL_2") (pin "1") (pinfunction "A_1") (pintype "unspecified"))
    )
    (net (code "52") (name "Net-(U1-A0)") (class "Default")
      (node (ref "A0MINI") (pin "1") (pinfunction "1_1") (pintype "unspecified"))
      (node (ref "U1") (pin "17") (pinfunction "A0_17") (pintype "unspecified"))
    )
    (net (code "53") (name "Net-(U1-D4)") (class "Default")
      (node (ref "R10") (pin "1") (pinfunction "1_1") (pintype "unspecified"))
      (node (ref "R12") (pin "2") (pinfunction "2_2") (pintype "unspecified"))
      (node (ref "U1") (pin "7") (pinfunction "D4_7") (pintype "unspecified"))
    )
    (net (code "54") (name "Net-(U1-D5)") (class "Default")
      (node (ref "R5") (pin "2") (pinfunction "2_2") (pintype "unspecified"))
      (node (ref "R8") (pin "1") (pinfunction "1_1") (pintype "unspecified"))
      (node (ref "U1") (pin "8") (pinfunction "D5_8") (pintype "unspecified"))
    )
    (net (code "55") (name "Net-(U1-D6)") (class "Default")
      (node (ref "R6") (pin "2") (pinfunction "2_2") (pintype "unspecified"))
      (node (ref "R9") (pin "1") (pinfunction "1_1") (pintype "unspecified"))
      (node (ref "U1") (pin "9") (pinfunction "D6_9") (pintype "unspecified"))
    )
    (net (code "56") (name "Net-(U1-D7)") (class "Default")
      (node (ref "R11") (pin "1") (pinfunction "1_1") (pintype "unspecified"))
      (node (ref "R14") (pin "2") (pinfunction "2_2") (pintype "unspecified"))
      (node (ref "U1") (pin "10") (pinfunction "D7_10") (pintype "unspecified"))
    )
    (net (code "57") (name "Net-(U1-D8)") (class "Default")
      (node (ref "RST") (pin "2") (pinfunction "2_2") (pintype "unspecified"))
      (node (ref "U1") (pin "11") (pinfunction "D8_11") (pintype "unspecified"))
    )
    (net (code "58") (name "Net-(U1-D9)") (class "Default")
      (node (ref "DC") (pin "2") (pinfunction "2_2") (pintype "unspecified"))
      (node (ref "U1") (pin "12") (pinfunction "D9_12") (pintype "unspecified"))
    )
    (net (code "59") (name "Net-(U1-D10)") (class "Default")
      (node (ref "A0NANO") (pin "1") (pinfunction "1_1") (pintype "unspecified"))
      (node (ref "D10MINI") (pin "2") (pinfunction "2_2") (pintype "unspecified"))
      (node (ref "U1") (pin "13") (pinfunction "D10_13") (pintype "unspecified"))
    )
    (net (code "60") (name "Net-(U1-D11)") (class "Default")
      (node (ref "D11MINI") (pin "2") (pinfunction "2_2") (pintype "unspecified"))
      (node (ref "U1") (pin "14") (pinfunction "D11_14") (pintype "unspecified"))
    )
    (net (code "61") (name "Net-(U1-D13)") (class "Default")
      (node (ref "D13MINI") (pin "2") (pinfunction "2_2") (pintype "unspecified"))
      (node (ref "U1") (pin "16") (pinfunction "D13_16") (pintype "unspecified"))
    )
    (net (code "62") (name "Net-(U1-DTR)") (class "Default")
      (node (ref "ISP") (pin "6") (pinfunction "6_6") (pintype "input"))
      (node (ref "U1") (pin "25") (pinfunction "DTR_25") (pintype "unspecified"))
    )
    (net (code "63") (name "Net-(U1-RAW)") (class "Default")
      (node (ref "U1") (pin "24") (pinfunction "RAW_24") (pintype "unspecified"))
      (node (ref "VINNANO") (pin "1") (pinfunction "1_1") (pintype "unspecified"))
    )
    (net (code "64") (name "VCC") (class "Default")
      (node (ref "C5") (pin "1") (pinfunction "1_1") (pintype "unspecified"))
      (node (ref "C6") (pin "1") (pinfunction "1_1") (pintype "unspecified"))
      (node (ref "C7") (pin "1") (pinfunction "1_1") (pintype "unspecified"))
      (node (ref "C8") (pin "1") (pinfunction "1_1") (pintype "unspecified"))
      (node (ref "D3") (pin "2") (pinfunction "-_2") (pintype "unspecified"))
      (node (ref "D5") (pin "2") (pinfunction "-_2") (pintype "unspecified"))
      (node (ref "F1") (pin "1") (pinfunction "1_1") (pintype "unspecified"))
      (node (ref "F2") (pin "2") (pinfunction "2_2") (pintype "unspecified"))
      (node (ref "X1") (pin "1") (pinfunction "12V_1") (pintype "unspecified"))
      (node (ref "X1") (pin "4") (pinfunction "12V_4") (pintype "unspecified"))
      (node (ref "X2") (pin "1") (pinfunction "FAN_1+_1") (pintype "unspecified"))
      (node (ref "X2") (pin "4") (pinfunction "FAN_2+_4") (pintype "unspecified"))
    )
    (net (code "65") (name "VinNano") (class "Default")
      (node (ref "C1") (pin "1") (pinfunction "1_1") (pintype "unspecified"))
      (node (ref "D1") (pin "1") (pinfunction "1_1") (pintype "unspecified"))
      (node (ref "U2") (pin "3") (pinfunction "In_3") (pintype "unspecified"))
      (node (ref "VINNANO") (pin "2") (pinfunction "2_2") (pintype "unspecified"))
    )
    (net (code "66") (name "i{slash}o_1") (class "Default")
      (node (ref "R28") (pin "2") (pinfunction "2_2") (pintype "unspecified"))
      (node (ref "R35") (pin "2") (pinfunction "2_2") (pintype "unspecified"))
      (node (ref "R7") (pin "2") (pinfunction "2_2") (pintype "unspecified"))
      (node (ref "U1") (pin "5") (pinfunction "D2_5") (pintype "unspecified"))
    )
    (net (code "67") (name "i{slash}o_2") (class "Default")
      (node (ref "R24") (pin "2") (pinfunction "2_2") (pintype "unspecified"))
      (node (ref "R29") (pin "2") (pinfunction "2_2") (pintype "unspecified"))
      (node (ref "R34") (pin "2") (pinfunction "2_2") (pintype "unspecified"))
      (node (ref "U1") (pin "6") (pinfunction "D3_6") (pintype "unspecified"))
    )
    (net (code "68") (name "i{slash}o_3") (class "Default")
      (node (ref "R25") (pin "2") (pinfunction "2_2") (pintype "unspecified"))
      (node (ref "R31") (pin "2") (pinfunction "2_2") (pintype "unspecified"))
      (node (ref "R37") (pin "2") (pinfunction "2_2") (pintype "unspecified"))
      (node (ref "U1") (pin "20") (pinfunction "A3_20") (pintype "unspecified"))
    )
    (net (code "69") (name "i{slash}o_4") (class "Default")
      (node (ref "R26") (pin "2") (pinfunction "2_2") (pintype "unspecified"))
      (node (ref "R30") (pin "2") (pinfunction "2_2") (pintype "unspecified"))
      (node (ref "R36") (pin "2") (pinfunction "2_2") (pintype "unspecified"))
      (node (ref "U1") (pin "19") (pinfunction "A2_19") (pintype "unspecified"))
    )
    (net (code "70") (name "i{slash}o_5") (class "Default")
      (node (ref "R27") (pin "2") (pinfunction "2_2") (pintype "unspecified"))
      (node (ref "R33") (pin "2") (pinfunction "2_2") (pintype "unspecified"))
      (node (ref "R40") (pin "2") (pinfunction "2_2") (pintype "unspecified"))
      (node (ref "U1") (pin "18") (pinfunction "A1_18") (pintype "unspecified"))
    )
    (net (code "71") (name "i{slash}o_6") (class "Default")
      (node (ref "R32") (pin "2") (pinfunction "2_2") (pintype "unspecified"))
      (node (ref "R38") (pin "2") (pinfunction "2_2") (pintype "unspecified"))
      (node (ref "R39") (pin "2") (pinfunction "2_2") (pintype "unspecified"))
      (node (ref "U1") (pin "15") (pinfunction "D12_15") (pintype "unspecified"))
    )
    (net (code "72") (name "unconnected-(U1-A4-Pad35)") (class "Default")
      (node (ref "U1") (pin "35") (pinfunction "A4_35") (pintype "unspecified"))
    )
    (net (code "73") (name "unconnected-(U1-A5-Pad34)") (class "Default")
      (node (ref "U1") (pin "34") (pinfunction "A5_34") (pintype "unspecified"))
    )
    (net (code "74") (name "unconnected-(U1-A6-Pad31)") (class "Default")
      (node (ref "U1") (pin "31") (pinfunction "A6_31") (pintype "unspecified"))
    )
    (net (code "75") (name "unconnected-(U1-A7-Pad32)") (class "Default")
      (node (ref "U1") (pin "32") (pinfunction "A7_32") (pintype "unspecified"))
    )
    (net (code "76") (name "unconnected-(U1-RST-Pad3)") (class "Default")
      (node (ref "U1") (pin "3") (pinfunction "RST_3") (pintype "unspecified"))
    )
    (net (code "77") (name "unconnected-(U1-RST-Pad22)") (class "Default")
      (node (ref "U1") (pin "22") (pinfunction "RST_22") (pintype "unspecified"))
    )
  )
)
